# loochi-0_3a.net
KiCad netlist of a schematic drawn in EAGLE
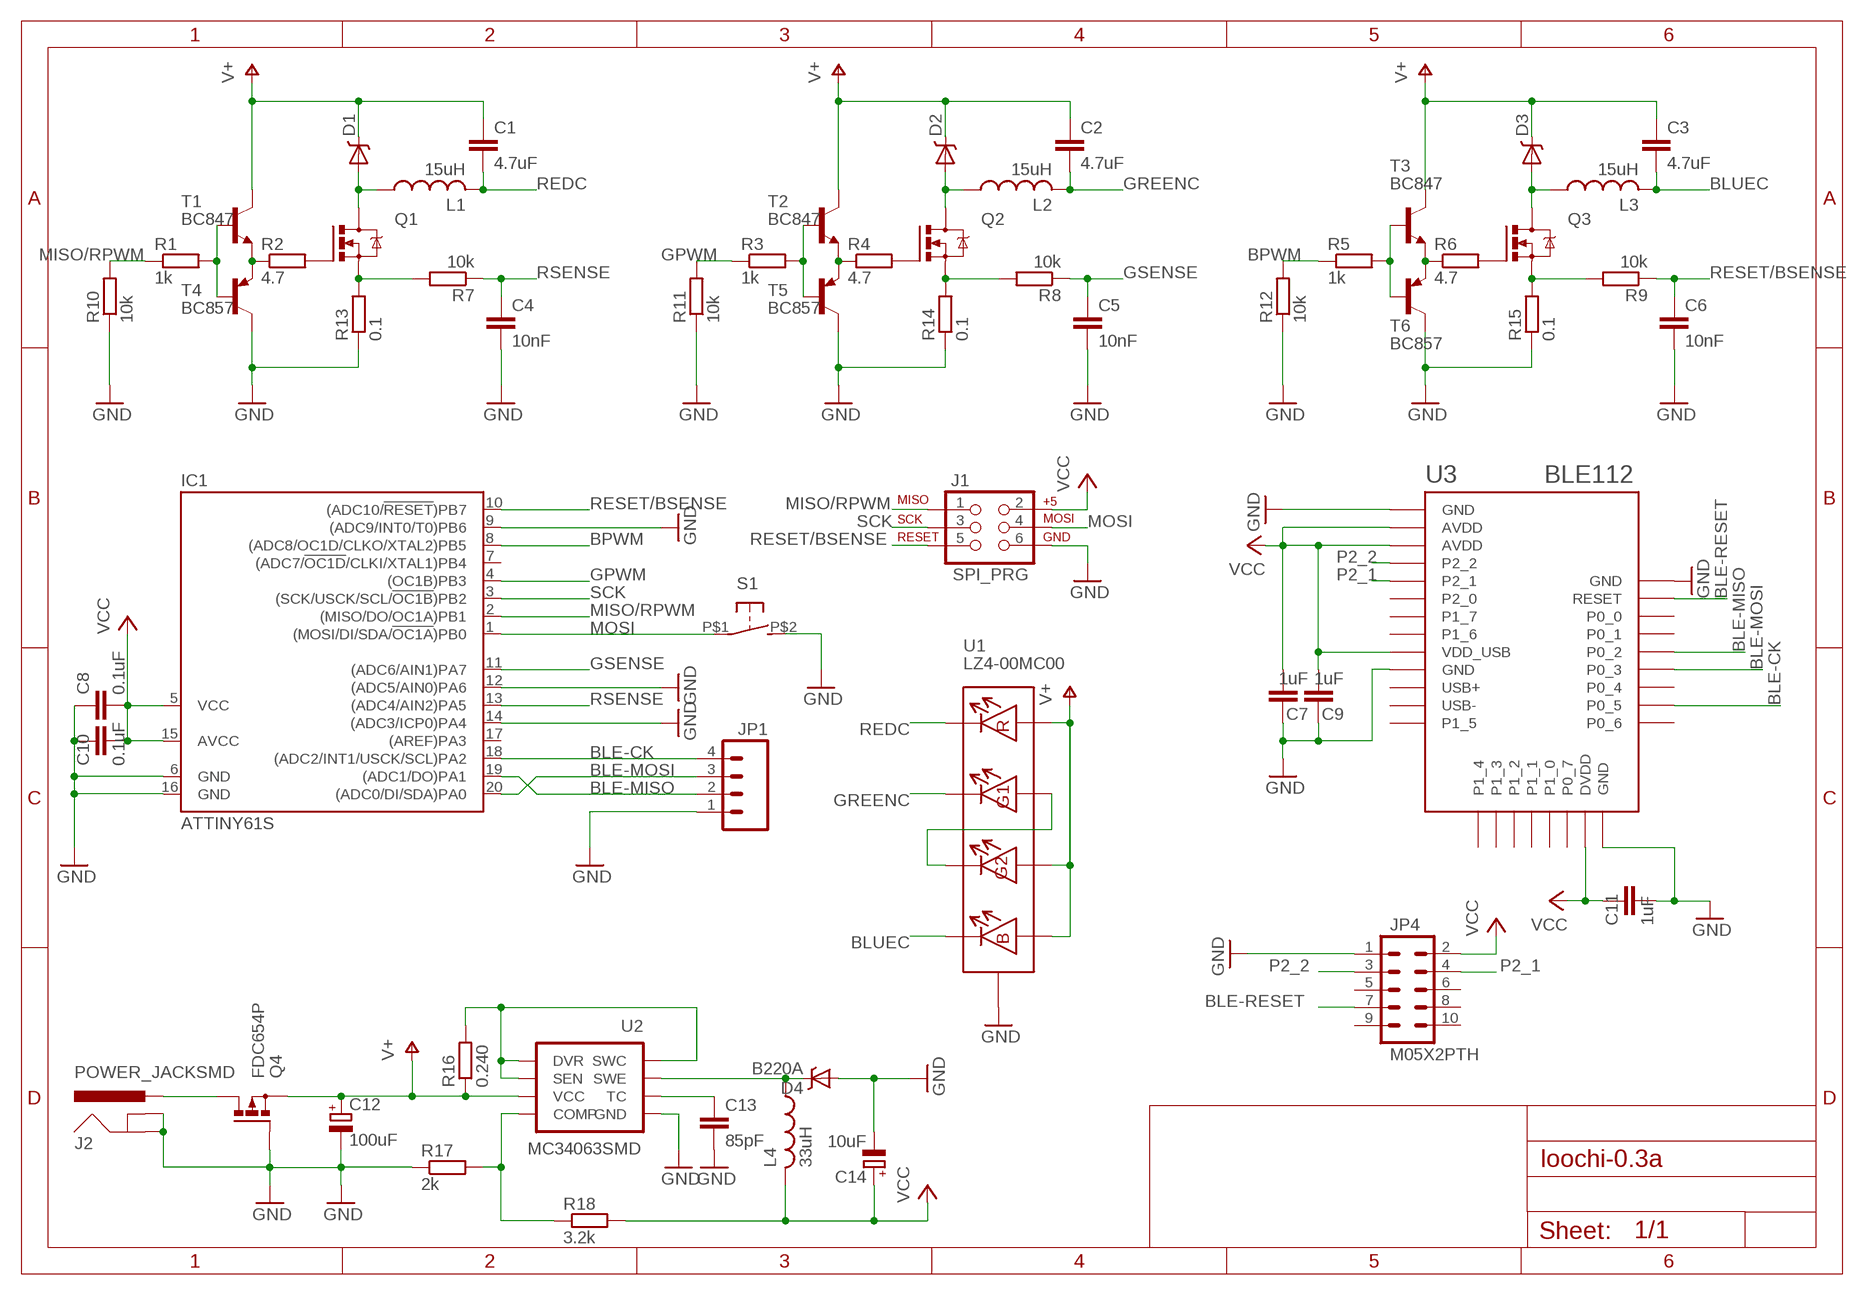
[diagram p0: schematic, sheet 1]

(export (version "E")
  (design (tool "Eeschema 10.0.6"))
  (components
    (comp (ref "C1")
      (value "4.7uF")
      (footprint "eagle-import:C0805")
      (libsource (lib "eagle-import") (part "C-EUC0805"))
    )
    (comp (ref "C2")
      (value "4.7uF")
      (footprint "eagle-import:C0805")
      (libsource (lib "eagle-import") (part "C-EUC0805"))
    )
    (comp (ref "C3")
      (value "4.7uF")
      (footprint "eagle-import:C0805")
      (libsource (lib "eagle-import") (part "C-EUC0805"))
    )
    (comp (ref "C4")
      (value "10nF")
      (footprint "eagle-import:C0805")
      (libsource (lib "eagle-import") (part "C-EUC0805"))
    )
    (comp (ref "C5")
      (value "10nF")
      (footprint "eagle-import:C0805")
      (libsource (lib "eagle-import") (part "C-EUC0805"))
    )
    (comp (ref "C6")
      (value "10nF")
      (footprint "eagle-import:C0805")
      (libsource (lib "eagle-import") (part "C-EUC0805"))
    )
    (comp (ref "C7")
      (value "1uF")
      (footprint "eagle-import:C0805")
      (libsource (lib "eagle-import") (part "C-EUC0805"))
    )
    (comp (ref "C8")
      (value "0.1uF")
      (footprint "eagle-import:C0805")
      (libsource (lib "eagle-import") (part "C-EUC0805"))
    )
    (comp (ref "C9")
      (value "1uF")
      (footprint "eagle-import:C0805")
      (libsource (lib "eagle-import") (part "C-EUC0805"))
    )
    (comp (ref "C10")
      (value "0.1uF")
      (footprint "eagle-import:C0805")
      (libsource (lib "eagle-import") (part "C-EUC0805"))
    )
    (comp (ref "C11")
      (value "1uF")
      (footprint "eagle-import:C0805")
      (libsource (lib "eagle-import") (part "C-EUC0805"))
    )
    (comp (ref "C12")
      (value "100uF")
      (footprint "eagle-import:PANASONIC_D")
      (libsource (lib "eagle-import") (part "CPOL-EUD"))
    )
    (comp (ref "C13")
      (value "85pF")
      (footprint "eagle-import:C0805")
      (libsource (lib "eagle-import") (part "C-EUC0805"))
    )
    (comp (ref "C14")
      (value "10uF")
      (footprint "eagle-import:UD-4X5,8_NICHICON")
      (libsource (lib "eagle-import") (part "CPOL-EUUD-4X5,8"))
    )
    (comp (ref "D1")
      (value "PMEG4010CEH")
      (footprint "eagle-import:SOD123F")
      (libsource (lib "eagle-import") (part "DIODE-SCHOTTKY"))
    )
    (comp (ref "D2")
      (value "PMEG4010CEH")
      (footprint "eagle-import:SOD123F")
      (libsource (lib "eagle-import") (part "DIODE-SCHOTTKY"))
    )
    (comp (ref "D3")
      (value "PMEG4010CEH")
      (footprint "eagle-import:SOD123F")
      (libsource (lib "eagle-import") (part "DIODE-SCHOTTKY"))
    )
    (comp (ref "D4")
      (value "B220A")
      (footprint "eagle-import:SMA-DIODE-BIG")
      (libsource (lib "eagle-import") (part "DIODE-SCHOTTKYBIGPAD"))
    )
    (comp (ref "IC1")
      (value "ATTINY61S")
      (footprint "eagle-import:SO20L")
      (fields (field (name "MPN") "ATTINY261-20SU"))
      (libsource (lib "eagle-import") (part "ATTINY61S"))
    )
    (comp (ref "J1")
      (value "SPI_PRG")
      (footprint "eagle-import:2X3-NS")
      (libsource (lib "eagle-import") (part "AVR_SPI_PRG_6NS"))
    )
    (comp (ref "J2")
      (value "POWER_JACKSMD")
      (footprint "eagle-import:POWER_JACK_SMD")
      (libsource (lib "eagle-import") (part "POWER_JACKSMD"))
    )
    (comp (ref "JP1")
      (value "M04PTH")
      (footprint "eagle-import:1X04")
      (libsource (lib "eagle-import") (part "M04PTH"))
    )
    (comp (ref "JP4")
      (value "M05X2PTH")
      (footprint "eagle-import:AVR_ICSP")
      (libsource (lib "eagle-import") (part "M05X2PTH"))
    )
    (comp (ref "L1")
      (value "15uH")
      (footprint "eagle-import:BOURNS-6045")
      (libsource (lib "eagle-import") (part "L-USBOURNS-6045"))
    )
    (comp (ref "L2")
      (value "15uH")
      (footprint "eagle-import:BOURNS-6045")
      (libsource (lib "eagle-import") (part "L-USBOURNS-6045"))
    )
    (comp (ref "L3")
      (value "15uH")
      (footprint "eagle-import:BOURNS-6045")
      (libsource (lib "eagle-import") (part "L-USBOURNS-6045"))
    )
    (comp (ref "L4")
      (value "33uH")
      (footprint "eagle-import:BOURNS-6045")
      (libsource (lib "eagle-import") (part "L-USBOURNS-6045"))
    )
    (comp (ref "Q1")
      (value "PMN25ENSOT457")
      (footprint "eagle-import:SOT457")
      (libsource (lib "eagle-import") (part "PMN25ENSOT457"))
    )
    (comp (ref "Q2")
      (value "PMN25ENSOT457")
      (footprint "eagle-import:SOT457")
      (libsource (lib "eagle-import") (part "PMN25ENSOT457"))
    )
    (comp (ref "Q3")
      (value "PMN25ENSOT457")
      (footprint "eagle-import:SOT457")
      (libsource (lib "eagle-import") (part "PMN25ENSOT457"))
    )
    (comp (ref "Q4")
      (value "FDC654P")
      (footprint "eagle-import:SUPERSOT6")
      (libsource (lib "eagle-import") (part "FDC654P"))
    )
    (comp (ref "R1")
      (value "1k")
      (footprint "eagle-import:R0805")
      (libsource (lib "eagle-import") (part "R-EU_R0805"))
    )
    (comp (ref "R2")
      (value "4.7")
      (footprint "eagle-import:R0805")
      (libsource (lib "eagle-import") (part "R-EU_R0805"))
    )
    (comp (ref "R3")
      (value "1k")
      (footprint "eagle-import:R0805")
      (libsource (lib "eagle-import") (part "R-EU_R0805"))
    )
    (comp (ref "R4")
      (value "4.7")
      (footprint "eagle-import:R0805")
      (libsource (lib "eagle-import") (part "R-EU_R0805"))
    )
    (comp (ref "R5")
      (value "1k")
      (footprint "eagle-import:R0805")
      (libsource (lib "eagle-import") (part "R-EU_R0805"))
    )
    (comp (ref "R6")
      (value "4.7")
      (footprint "eagle-import:R0805")
      (libsource (lib "eagle-import") (part "R-EU_R0805"))
    )
    (comp (ref "R7")
      (value "10k")
      (footprint "eagle-import:R0805")
      (libsource (lib "eagle-import") (part "R-EU_R0805"))
    )
    (comp (ref "R8")
      (value "10k")
      (footprint "eagle-import:R0805")
      (libsource (lib "eagle-import") (part "R-EU_R0805"))
    )
    (comp (ref "R9")
      (value "10k")
      (footprint "eagle-import:R0805")
      (libsource (lib "eagle-import") (part "R-EU_R0805"))
    )
    (comp (ref "R10")
      (value "10k")
      (footprint "eagle-import:R0805")
      (libsource (lib "eagle-import") (part "R-EU_R0805"))
    )
    (comp (ref "R11")
      (value "10k")
      (footprint "eagle-import:R0805")
      (libsource (lib "eagle-import") (part "R-EU_R0805"))
    )
    (comp (ref "R12")
      (value "10k")
      (footprint "eagle-import:R0805")
      (libsource (lib "eagle-import") (part "R-EU_R0805"))
    )
    (comp (ref "R13")
      (value "0.1")
      (footprint "eagle-import:R0805")
      (libsource (lib "eagle-import") (part "R-EU_R0805"))
    )
    (comp (ref "R14")
      (value "0.1")
      (footprint "eagle-import:R0805")
      (libsource (lib "eagle-import") (part "R-EU_R0805"))
    )
    (comp (ref "R15")
      (value "0.1")
      (footprint "eagle-import:R0805")
      (libsource (lib "eagle-import") (part "R-EU_R0805"))
    )
    (comp (ref "R16")
      (value "0.240")
      (footprint "eagle-import:R0805")
      (libsource (lib "eagle-import") (part "R-EU_R0805"))
    )
    (comp (ref "R17")
      (value "2k")
      (footprint "eagle-import:R0805")
      (libsource (lib "eagle-import") (part "R-EU_R0805"))
    )
    (comp (ref "R18")
      (value "3.2k")
      (footprint "eagle-import:R0805")
      (libsource (lib "eagle-import") (part "R-EU_R0805"))
    )
    (comp (ref "S1")
      (value "ALPS-SKRK39X29")
      (footprint "eagle-import:ALPS-SKRK-39X29")
      (libsource (lib "eagle-import") (part "ALPS-SKRK39X29"))
    )
    (comp (ref "T1")
      (value "BC847")
      (footprint "eagle-import:SOT23")
      (libsource (lib "eagle-import") (part "BC847"))
    )
    (comp (ref "T2")
      (value "BC847")
      (footprint "eagle-import:SOT23")
      (libsource (lib "eagle-import") (part "BC847"))
    )
    (comp (ref "T3")
      (value "BC847")
      (footprint "eagle-import:SOT23")
      (libsource (lib "eagle-import") (part "BC847"))
    )
    (comp (ref "T4")
      (value "BC857")
      (footprint "eagle-import:SOT23-BEC")
      (libsource (lib "eagle-import") (part "-PNP-SOT23-BECBC857A"))
    )
    (comp (ref "T5")
      (value "BC857")
      (footprint "eagle-import:SOT23-BEC")
      (libsource (lib "eagle-import") (part "-PNP-SOT23-BECBC857A"))
    )
    (comp (ref "T6")
      (value "BC857")
      (footprint "eagle-import:SOT23-BEC")
      (libsource (lib "eagle-import") (part "-PNP-SOT23-BECBC857A"))
    )
    (comp (ref "U1")
      (value "LZ4-00MC00")
      (footprint "eagle-import:LZ4-00MC00")
      (libsource (lib "eagle-import") (part "LZ4-00MC00"))
    )
    (comp (ref "U2")
      (value "MC34063SMD")
      (footprint "eagle-import:SO08")
      (libsource (lib "eagle-import") (part "MC34063SMD"))
    )
    (comp (ref "U3")
      (value "BLE112")
      (footprint "eagle-import:SF-BLUEGIGA_BLE112-A")
      (libsource (lib "eagle-import") (part "SF-BLUEGIGA_BLE112-A-VISUAL"))
    )
  )
  (nets
    (net (code "1") (name "/BLE-CK") (class "Default")
      (node (ref "IC1") (pin "18") (pinfunction "(ADC2/INT1/USCK/SCL)PA2_18") (pintype "bidirectional"))
      (node (ref "JP1") (pin "4") (pinfunction "4_4") (pintype "passive"))
      (node (ref "U3") (pin "P0_5") (pinfunction "P0_5_P0_5") (pintype "bidirectional"))
    )
    (net (code "2") (name "/BLE-MISO") (class "Default")
      (node (ref "IC1") (pin "19") (pinfunction "(ADC1/DO)PA1_19") (pintype "bidirectional"))
      (node (ref "JP1") (pin "2") (pinfunction "2_2") (pintype "passive"))
      (node (ref "U3") (pin "P0_2") (pinfunction "P0_2_P0_2") (pintype "bidirectional"))
    )
    (net (code "3") (name "/BLE-MOSI") (class "Default")
      (node (ref "IC1") (pin "20") (pinfunction "(ADC0/DI/SDA)PA0_20") (pintype "bidirectional"))
      (node (ref "JP1") (pin "3") (pinfunction "3_3") (pintype "passive"))
      (node (ref "U3") (pin "P0_3") (pinfunction "P0_3_P0_3") (pintype "bidirectional"))
    )
    (net (code "4") (name "/BLE-RESET") (class "Default")
      (node (ref "JP4") (pin "7") (pinfunction "7_7") (pintype "passive"))
      (node (ref "U3") (pin "RESET") (pinfunction "RESET_RESET") (pintype "input"))
    )
    (net (code "5") (name "/BLUEC") (class "Default")
      (node (ref "C3") (pin "2") (pinfunction "2_2") (pintype "passive"))
      (node (ref "L3") (pin "P$2") (pinfunction "2_P$2") (pintype "passive"))
      (node (ref "U1") (pin "P$8") (pinfunction "P$8_P$8") (pintype "bidirectional"))
    )
    (net (code "6") (name "/BPWM") (class "Default")
      (node (ref "IC1") (pin "8") (pinfunction "(ADC8/OC1D/CLKO/XTAL2)PB5_8") (pintype "bidirectional"))
      (node (ref "R12") (pin "2") (pinfunction "2_2") (pintype "passive"))
      (node (ref "R5") (pin "1") (pinfunction "1_1") (pintype "passive"))
    )
    (net (code "7") (name "/GPWM") (class "Default")
      (node (ref "IC1") (pin "4") (pinfunction "(OC1B)PB3_4") (pintype "bidirectional"))
      (node (ref "R11") (pin "2") (pinfunction "2_2") (pintype "passive"))
      (node (ref "R3") (pin "1") (pinfunction "1_1") (pintype "passive"))
    )
    (net (code "8") (name "/GREENC") (class "Default")
      (node (ref "C2") (pin "2") (pinfunction "2_2") (pintype "passive"))
      (node (ref "L2") (pin "P$2") (pinfunction "2_P$2") (pintype "passive"))
      (node (ref "U1") (pin "P$6") (pinfunction "P$6_P$6") (pintype "bidirectional"))
    )
    (net (code "9") (name "/GSENSE") (class "Default")
      (node (ref "C5") (pin "1") (pinfunction "1_1") (pintype "passive"))
      (node (ref "IC1") (pin "11") (pinfunction "(ADC6/AIN1)PA7_11") (pintype "bidirectional"))
      (node (ref "R8") (pin "1") (pinfunction "1_1") (pintype "passive"))
    )
    (net (code "10") (name "/MISO{slash}RPWM") (class "Default")
      (node (ref "IC1") (pin "2") (pinfunction "(MISO/DO/OC1A)PB1_2") (pintype "bidirectional"))
      (node (ref "J1") (pin "1") (pinfunction "1_1") (pintype "passive"))
      (node (ref "R1") (pin "1") (pinfunction "1_1") (pintype "passive"))
      (node (ref "R10") (pin "2") (pinfunction "2_2") (pintype "passive"))
    )
    (net (code "11") (name "/MOSI") (class "Default")
      (node (ref "IC1") (pin "1") (pinfunction "(MOSI/DI/SDA/~{OC1A})PB0_1") (pintype "bidirectional"))
      (node (ref "J1") (pin "4") (pinfunction "4_4") (pintype "passive"))
      (node (ref "S1") (pin "P$1") (pinfunction "P_P$1") (pintype "passive"))
    )
    (net (code "12") (name "/P2_1") (class "Default")
      (node (ref "JP4") (pin "4") (pinfunction "4_4") (pintype "passive"))
      (node (ref "U3") (pin "P2_1") (pinfunction "P2_1_P2_1") (pintype "bidirectional"))
    )
    (net (code "13") (name "/P2_2") (class "Default")
      (node (ref "JP4") (pin "3") (pinfunction "3_3") (pintype "passive"))
      (node (ref "U3") (pin "P2_2") (pinfunction "P2_2_P2_2") (pintype "bidirectional"))
    )
    (net (code "14") (name "/REDC") (class "Default")
      (node (ref "C1") (pin "2") (pinfunction "2_2") (pintype "passive"))
      (node (ref "L1") (pin "P$2") (pinfunction "2_P$2") (pintype "passive"))
      (node (ref "U1") (pin "P$4") (pinfunction "P$4_P$4") (pintype "bidirectional"))
    )
    (net (code "15") (name "/RESET{slash}BSENSE") (class "Default")
      (node (ref "C6") (pin "1") (pinfunction "1_1") (pintype "passive"))
      (node (ref "IC1") (pin "10") (pinfunction "(ADC10/~{RESET})PB7_10") (pintype "bidirectional"))
      (node (ref "J1") (pin "5") (pinfunction "5_5") (pintype "passive"))
      (node (ref "R9") (pin "1") (pinfunction "1_1") (pintype "passive"))
    )
    (net (code "16") (name "/RSENSE") (class "Default")
      (node (ref "C4") (pin "1") (pinfunction "1_1") (pintype "passive"))
      (node (ref "IC1") (pin "13") (pinfunction "(ADC4/AIN2)PA5_13") (pintype "bidirectional"))
      (node (ref "R7") (pin "1") (pinfunction "1_1") (pintype "passive"))
    )
    (net (code "17") (name "/SCK") (class "Default")
      (node (ref "IC1") (pin "3") (pinfunction "(SCK/USCK/SCL/~{OC1B})PB2_3") (pintype "bidirectional"))
      (node (ref "J1") (pin "3") (pinfunction "3_3") (pintype "passive"))
    )
    (net (code "18") (name "GND") (class "Default")
      (node (ref "C10") (pin "1") (pinfunction "1_1") (pintype "passive"))
      (node (ref "C11") (pin "2") (pinfunction "2_2") (pintype "passive"))
      (node (ref "C12") (pin "-") (pinfunction "-_-") (pintype "passive"))
      (node (ref "C13") (pin "2") (pinfunction "2_2") (pintype "passive"))
      (node (ref "C14") (pin "-") (pinfunction "-_-") (pintype "passive"))
      (node (ref "C4") (pin "2") (pinfunction "2_2") (pintype "passive"))
      (node (ref "C5") (pin "2") (pinfunction "2_2") (pintype "passive"))
      (node (ref "C6") (pin "2") (pinfunction "2_2") (pintype "passive"))
      (node (ref "C7") (pin "1") (pinfunction "1_1") (pintype "passive"))
      (node (ref "C8") (pin "1") (pinfunction "1_1") (pintype "passive"))
      (node (ref "C9") (pin "1") (pinfunction "1_1") (pintype "passive"))
      (node (ref "D4") (pin "A") (pinfunction "A_A") (pintype "passive"))
      (node (ref "IC1") (pin "12") (pinfunction "(ADC5/AIN0)PA6_12") (pintype "bidirectional"))
      (node (ref "IC1") (pin "14") (pinfunction "(ADC3/ICP0)PA4_14") (pintype "bidirectional"))
      (node (ref "IC1") (pin "16") (pinfunction "GND_16") (pintype "power_in"))
      (node (ref "IC1") (pin "6") (pinfunction "GND_6") (pintype "power_in"))
      (node (ref "IC1") (pin "9") (pinfunction "(ADC9/INT0/T0)PB6_9") (pintype "bidirectional"))
      (node (ref "J1") (pin "6") (pinfunction "6_6") (pintype "passive"))
      (node (ref "J2") (pin "GND") (pinfunction "GNDBREAK_GND") (pintype "bidirectional"))
      (node (ref "J2") (pin "P$4") (pinfunction "GND_P$4") (pintype "bidirectional"))
      (node (ref "JP1") (pin "1") (pinfunction "1_1") (pintype "passive"))
      (node (ref "JP4") (pin "1") (pinfunction "1_1") (pintype "passive"))
      (node (ref "Q4") (pin "P$3") (pinfunction "G_P$3") (pintype "passive"))
      (node (ref "R10") (pin "1") (pinfunction "1_1") (pintype "passive"))
      (node (ref "R11") (pin "1") (pinfunction "1_1") (pintype "passive"))
      (node (ref "R12") (pin "1") (pinfunction "1_1") (pintype "passive"))
      (node (ref "R13") (pin "1") (pinfunction "1_1") (pintype "passive"))
      (node (ref "R14") (pin "1") (pinfunction "1_1") (pintype "passive"))
      (node (ref "R15") (pin "1") (pinfunction "1_1") (pintype "passive"))
      (node (ref "R17") (pin "1") (pinfunction "1_1") (pintype "passive"))
      (node (ref "S1") (pin "P$2") (pinfunction "S_P$2") (pintype "passive"))
      (node (ref "T4") (pin "C") (pinfunction "C_C") (pintype "passive"))
      (node (ref "T5") (pin "C") (pinfunction "C_C") (pintype "passive"))
      (node (ref "T6") (pin "C") (pinfunction "C_C") (pintype "passive"))
      (node (ref "U1") (pin "THERMAL") (pinfunction "THERMAL_THERMAL") (pintype "bidirectional"))
      (node (ref "U1") (pin "THERMAL-VIA") (pinfunction "THERMAL_THERMAL-VIA") (pintype "bidirectional"))
      (node (ref "U1") (pin "THERMAL-VIA2") (pinfunction "THERMAL_THERMAL-VIA2") (pintype "bidirectional"))
      (node (ref "U2") (pin "4") (pinfunction "GND_4") (pintype "bidirectional"))
      (node (ref "U3") (pin "GND1") (pinfunction "GND_GND1") (pintype "power_in"))
      (node (ref "U3") (pin "GND2") (pinfunction "GND_GND2") (pintype "power_in"))
      (node (ref "U3") (pin "GND3") (pinfunction "GND_GND3") (pintype "power_in"))
      (node (ref "U3") (pin "GND4") (pinfunction "GND_GND4") (pintype "power_in"))
    )
    (net (code "19") (name "Net-(D1-A)") (class "Default")
      (node (ref "D1") (pin "P$A") (pinfunction "A_P$A") (pintype "passive"))
      (node (ref "L1") (pin "P$1") (pinfunction "1_P$1") (pintype "passive"))
      (node (ref "Q1") (pin "P$1") (pinfunction "D_P$1") (pintype "passive"))
      (node (ref "Q1") (pin "P$2") (pinfunction "D_P$2") (pintype "passive"))
      (node (ref "Q1") (pin "P$5") (pinfunction "D_P$5") (pintype "passive"))
      (node (ref "Q1") (pin "P$6") (pinfunction "D_P$6") (pintype "passive"))
    )
    (net (code "20") (name "Net-(D2-A)") (class "Default")
      (node (ref "D2") (pin "P$A") (pinfunction "A_P$A") (pintype "passive"))
      (node (ref "L2") (pin "P$1") (pinfunction "1_P$1") (pintype "passive"))
      (node (ref "Q2") (pin "P$1") (pinfunction "D_P$1") (pintype "passive"))
      (node (ref "Q2") (pin "P$2") (pinfunction "D_P$2") (pintype "passive"))
      (node (ref "Q2") (pin "P$5") (pinfunction "D_P$5") (pintype "passive"))
      (node (ref "Q2") (pin "P$6") (pinfunction "D_P$6") (pintype "passive"))
    )
    (net (code "21") (name "Net-(D3-A)") (class "Default")
      (node (ref "D3") (pin "P$A") (pinfunction "A_P$A") (pintype "passive"))
      (node (ref "L3") (pin "P$1") (pinfunction "1_P$1") (pintype "passive"))
      (node (ref "Q3") (pin "P$1") (pinfunction "D_P$1") (pintype "passive"))
      (node (ref "Q3") (pin "P$2") (pinfunction "D_P$2") (pintype "passive"))
      (node (ref "Q3") (pin "P$5") (pinfunction "D_P$5") (pintype "passive"))
      (node (ref "Q3") (pin "P$6") (pinfunction "D_P$6") (pintype "passive"))
    )
    (net (code "22") (name "Net-(J2-PWR-PadVIN0)") (class "Default")
      (node (ref "J2") (pin "VIN0") (pinfunction "PWR_VIN0") (pintype "bidirectional"))
      (node (ref "J2") (pin "VIN1") (pinfunction "PWR_VIN1") (pintype "bidirectional"))
      (node (ref "Q4") (pin "P$1") (pinfunction "D_P$1") (pintype "passive"))
      (node (ref "Q4") (pin "P$2") (pinfunction "D_P$2") (pintype "passive"))
      (node (ref "Q4") (pin "P$5") (pinfunction "D_P$5") (pintype "passive"))
      (node (ref "Q4") (pin "P$6") (pinfunction "D_P$6") (pintype "passive"))
    )
    (net (code "23") (name "Net-(L4-1)") (class "Default")
      (node (ref "D4") (pin "C") (pinfunction "C_C") (pintype "passive"))
      (node (ref "L4") (pin "P$1") (pinfunction "1_P$1") (pintype "passive"))
      (node (ref "U2") (pin "2") (pinfunction "SWE_2") (pintype "bidirectional"))
    )
    (net (code "24") (name "Net-(Q1-G)") (class "Default")
      (node (ref "Q1") (pin "P$3") (pinfunction "G_P$3") (pintype "passive"))
      (node (ref "R2") (pin "2") (pinfunction "2_2") (pintype "passive"))
    )
    (net (code "25") (name "Net-(Q1-S)") (class "Default")
      (node (ref "Q1") (pin "P$4") (pinfunction "S_P$4") (pintype "passive"))
      (node (ref "R13") (pin "2") (pinfunction "2_2") (pintype "passive"))
      (node (ref "R7") (pin "2") (pinfunction "2_2") (pintype "passive"))
    )
    (net (code "26") (name "Net-(Q2-G)") (class "Default")
      (node (ref "Q2") (pin "P$3") (pinfunction "G_P$3") (pintype "passive"))
      (node (ref "R4") (pin "2") (pinfunction "2_2") (pintype "passive"))
    )
    (net (code "27") (name "Net-(Q2-S)") (class "Default")
      (node (ref "Q2") (pin "P$4") (pinfunction "S_P$4") (pintype "passive"))
      (node (ref "R14") (pin "2") (pinfunction "2_2") (pintype "passive"))
      (node (ref "R8") (pin "2") (pinfunction "2_2") (pintype "passive"))
    )
    (net (code "28") (name "Net-(Q3-G)") (class "Default")
      (node (ref "Q3") (pin "P$3") (pinfunction "G_P$3") (pintype "passive"))
      (node (ref "R6") (pin "2") (pinfunction "2_2") (pintype "passive"))
    )
    (net (code "29") (name "Net-(Q3-S)") (class "Default")
      (node (ref "Q3") (pin "P$4") (pinfunction "S_P$4") (pintype "passive"))
      (node (ref "R15") (pin "2") (pinfunction "2_2") (pintype "passive"))
      (node (ref "R9") (pin "2") (pinfunction "2_2") (pintype "passive"))
    )
    (net (code "30") (name "Net-(T1-B)") (class "Default")
      (node (ref "R1") (pin "2") (pinfunction "2_2") (pintype "passive"))
      (node (ref "T1") (pin "1") (pinfunction "B_1") (pintype "passive"))
      (node (ref "T4") (pin "B") (pinfunction "B_B") (pintype "passive"))
    )
    (net (code "31") (name "Net-(T1-E)") (class "Default")
      (node (ref "R2") (pin "1") (pinfunction "1_1") (pintype "passive"))
      (node (ref "T1") (pin "2") (pinfunction "E_2") (pintype "passive"))
      (node (ref "T4") (pin "E") (pinfunction "E_E") (pintype "passive"))
    )
    (net (code "32") (name "Net-(T2-B)") (class "Default")
      (node (ref "R3") (pin "2") (pinfunction "2_2") (pintype "passive"))
      (node (ref "T2") (pin "1") (pinfunction "B_1") (pintype "passive"))
      (node (ref "T5") (pin "B") (pinfunction "B_B") (pintype "passive"))
    )
    (net (code "33") (name "Net-(T2-E)") (class "Default")
      (node (ref "R4") (pin "1") (pinfunction "1_1") (pintype "passive"))
      (node (ref "T2") (pin "2") (pinfunction "E_2") (pintype "passive"))
      (node (ref "T5") (pin "E") (pinfunction "E_E") (pintype "passive"))
    )
    (net (code "34") (name "Net-(T3-B)") (class "Default")
      (node (ref "R5") (pin "2") (pinfunction "2_2") (pintype "passive"))
      (node (ref "T3") (pin "1") (pinfunction "B_1") (pintype "passive"))
      (node (ref "T6") (pin "B") (pinfunction "B_B") (pintype "passive"))
    )
    (net (code "35") (name "Net-(T3-E)") (class "Default")
      (node (ref "R6") (pin "1") (pinfunction "1_1") (pintype "passive"))
      (node (ref "T3") (pin "2") (pinfunction "E_2") (pintype "passive"))
      (node (ref "T6") (pin "E") (pinfunction "E_E") (pintype "passive"))
    )
    (net (code "36") (name "Net-(U1-P$2)") (class "Default")
      (node (ref "U1") (pin "P$1") (pinfunction "P$2_P$1") (pintype "bidirectional"))
      (node (ref "U1") (pin "P$5") (pinfunction "P$5_P$5") (pintype "bidirectional"))
    )
    (net (code "37") (name "Net-(U2-COMP)") (class "Default")
      (node (ref "R17") (pin "2") (pinfunction "2_2") (pintype "passive"))
      (node (ref "R18") (pin "1") (pinfunction "1_1") (pintype "passive"))
      (node (ref "U2") (pin "5") (pinfunction "COMP_5") (pintype "bidirectional"))
    )
    (net (code "38") (name "Net-(U2-DVR)") (class "Default")
      (node (ref "R16") (pin "2") (pinfunction "2_2") (pintype "passive"))
      (node (ref "U2") (pin "1") (pinfunction "SWC_1") (pintype "bidirectional"))
      (node (ref "U2") (pin "7") (pinfunction "SEN_7") (pintype "bidirectional"))
      (node (ref "U2") (pin "8") (pinfunction "DVR_8") (pintype "bidirectional"))
    )
    (net (code "39") (name "Net-(U2-TC)") (class "Default")
      (node (ref "C13") (pin "1") (pinfunction "1_1") (pintype "passive"))
      (node (ref "U2") (pin "3") (pinfunction "TC_3") (pintype "bidirectional"))
    )
    (net (code "40") (name "V+") (class "Default")
      (node (ref "C1") (pin "1") (pinfunction "1_1") (pintype "passive"))
      (node (ref "C12") (pin "+") (pinfunction "+_+") (pintype "passive"))
      (node (ref "C2") (pin "1") (pinfunction "1_1") (pintype "passive"))
      (node (ref "C3") (pin "1") (pinfunction "1_1") (pintype "passive"))
      (node (ref "D1") (pin "P$C") (pinfunction "C_P$C") (pintype "passive"))
      (node (ref "D2") (pin "P$C") (pinfunction "C_P$C") (pintype "passive"))
      (node (ref "D3") (pin "P$C") (pinfunction "C_P$C") (pintype "passive"))
      (node (ref "Q4") (pin "P$4") (pinfunction "S_P$4") (pintype "passive"))
      (node (ref "R16") (pin "1") (pinfunction "1_1") (pintype "passive"))
      (node (ref "T1") (pin "3") (pinfunction "C_3") (pintype "passive"))
      (node (ref "T2") (pin "3") (pinfunction "C_3") (pintype "passive"))
      (node (ref "T3") (pin "3") (pinfunction "C_3") (pintype "passive"))
      (node (ref "U1") (pin "P$2") (pinfunction "P$3_P$2") (pintype "bidirectional"))
      (node (ref "U1") (pin "P$3") (pinfunction "P$1_P$3") (pintype "bidirectional"))
      (node (ref "U1") (pin "P$7") (pinfunction "P$7_P$7") (pintype "bidirectional"))
      (node (ref "U2") (pin "6") (pinfunction "VCC_6") (pintype "bidirectional"))
    )
    (net (code "41") (name "VCC") (class "Default")
      (node (ref "C10") (pin "2") (pinfunction "2_2") (pintype "passive"))
      (node (ref "C11") (pin "1") (pinfunction "1_1") (pintype "passive"))
      (node (ref "C14") (pin "+") (pinfunction "+_+") (pintype "passive"))
      (node (ref "C7") (pin "2") (pinfunction "2_2") (pintype "passive"))
      (node (ref "C8") (pin "2") (pinfunction "2_2") (pintype "passive"))
      (node (ref "C9") (pin "2") (pinfunction "2_2") (pintype "passive"))
      (node (ref "IC1") (pin "15") (pinfunction "AVCC_15") (pintype "power_in"))
      (node (ref "IC1") (pin "5") (pinfunction "VCC_5") (pintype "power_in"))
      (node (ref "J1") (pin "2") (pinfunction "2_2") (pintype "passive"))
      (node (ref "JP4") (pin "2") (pinfunction "2_2") (pintype "passive"))
      (node (ref "L4") (pin "P$2") (pinfunction "2_P$2") (pintype "passive"))
      (node (ref "R18") (pin "2") (pinfunction "2_2") (pintype "passive"))
      (node (ref "U3") (pin "AVDD1") (pinfunction "AVDD_AVDD1") (pintype "power_in"))
      (node (ref "U3") (pin "AVDD2") (pinfunction "AVDD_AVDD2") (pintype "power_in"))
      (node (ref "U3") (pin "DVDD") (pinfunction "DVDD_DVDD") (pintype "power_in"))
      (node (ref "U3") (pin "VDD_USB") (pinfunction "VDD_USB_VDD_USB") (pintype "power_in"))
    )
    (net (code "42") (name "unconnected-(IC1-(ADC7{slash}~{OC1D}{slash}CLKI{slash}XTAL1)PB4-Pad7)") (class "Default")
      (node (ref "IC1") (pin "7") (pinfunction "(ADC7/~{OC1D}/CLKI/XTAL1)PB4_7") (pintype "bidirectional"))
    )
    (net (code "43") (name "unconnected-(IC1-(AREF)PA3-Pad17)") (class "Default")
      (node (ref "IC1") (pin "17") (pinfunction "(AREF)PA3_17") (pintype "bidirectional"))
    )
    (net (code "44") (name "unconnected-(JP4-Pad5)") (class "Default")
      (node (ref "JP4") (pin "5") (pinfunction "5_5") (pintype "passive"))
    )
    (net (code "45") (name "unconnected-(JP4-Pad6)") (class "Default")
      (node (ref "JP4") (pin "6") (pinfunction "6_6") (pintype "passive"))
    )
    (net (code "46") (name "unconnected-(JP4-Pad8)") (class "Default")
      (node (ref "JP4") (pin "8") (pinfunction "8_8") (pintype "passive"))
    )
    (net (code "47") (name "unconnected-(JP4-Pad9)") (class "Default")
      (node (ref "JP4") (pin "9") (pinfunction "9_9") (pintype "passive"))
    )
    (net (code "48") (name "unconnected-(JP4-Pad10)") (class "Default")
      (node (ref "JP4") (pin "10") (pinfunction "10_10") (pintype "passive"))
    )
    (net (code "49") (name "unconnected-(U3-PadP0_0)") (class "Default")
      (node (ref "U3") (pin "P0_0") (pinfunction "P0_0_P0_0") (pintype "bidirectional"))
    )
    (net (code "50") (name "unconnected-(U3-PadP0_1)") (class "Default")
      (node (ref "U3") (pin "P0_1") (pinfunction "P0_1_P0_1") (pintype "bidirectional"))
    )
    (net (code "51") (name "unconnected-(U3-PadP0_4)") (class "Default")
      (node (ref "U3") (pin "P0_4") (pinfunction "P0_4_P0_4") (pintype "bidirectional"))
    )
    (net (code "52") (name "unconnected-(U3-PadP0_6)") (class "Default")
      (node (ref "U3") (pin "P0_6") (pinfunction "P0_6_P0_6") (pintype "bidirectional"))
    )
    (net (code "53") (name "unconnected-(U3-PadP0_7)") (class "Default")
      (node (ref "U3") (pin "P0_7") (pinfunction "P0_7_P0_7") (pintype "bidirectional"))
    )
    (net (code "54") (name "unconnected-(U3-PadP1_0)") (class "Default")
      (node (ref "U3") (pin "P1_0") (pinfunction "P1_0_P1_0") (pintype "bidirectional"))
    )
    (net (code "55") (name "unconnected-(U3-PadP1_1)") (class "Default")
      (node (ref "U3") (pin "P1_1") (pinfunction "P1_1_P1_1") (pintype "bidirectional"))
    )
    (net (code "56") (name "unconnected-(U3-PadP1_2)") (class "Default")
      (node (ref "U3") (pin "P1_2") (pinfunction "P1_2_P1_2") (pintype "bidirectional"))
    )
    (net (code "57") (name "unconnected-(U3-PadP1_3)") (class "Default")
      (node (ref "U3") (pin "P1_3") (pinfunction "P1_3_P1_3") (pintype "bidirectional"))
    )
    (net (code "58") (name "unconnected-(U3-PadP1_4)") (class "Default")
      (node (ref "U3") (pin "P1_4") (pinfunction "P1_4_P1_4") (pintype "bidirectional"))
    )
    (net (code "59") (name "unconnected-(U3-PadP1_5)") (class "Default")
      (node (ref "U3") (pin "P1_5") (pinfunction "P1_5_P1_5") (pintype "bidirectional"))
    )
    (net (code "60") (name "unconnected-(U3-PadP1_6)") (class "Default")
      (node (ref "U3") (pin "P1_6") (pinfunction "P1_6_P1_6") (pintype "bidirectional"))
    )
    (net (code "61") (name "unconnected-(U3-PadP1_7)") (class "Default")
      (node (ref "U3") (pin "P1_7") (pinfunction "P1_7_P1_7") (pintype "bidirectional"))
    )
    (net (code "62") (name "unconnected-(U3-PadP2_0)") (class "Default")
      (node (ref "U3") (pin "P2_0") (pinfunction "P2_0_P2_0") (pintype "bidirectional"))
    )
    (net (code "63") (name "unconnected-(U3-PadUSB+)") (class "Default")
      (node (ref "U3") (pin "USB+") (pinfunction "USB+_USB+") (pintype "bidirectional"))
    )
    (net (code "64") (name "unconnected-(U3-PadUSB-)") (class "Default")
      (node (ref "U3") (pin "USB-") (pinfunction "USB-_USB-") (pintype "bidirectional"))
    )
  )
)
